# schematic.net
KiCad netlist of a schematic drawn in EasyEDA
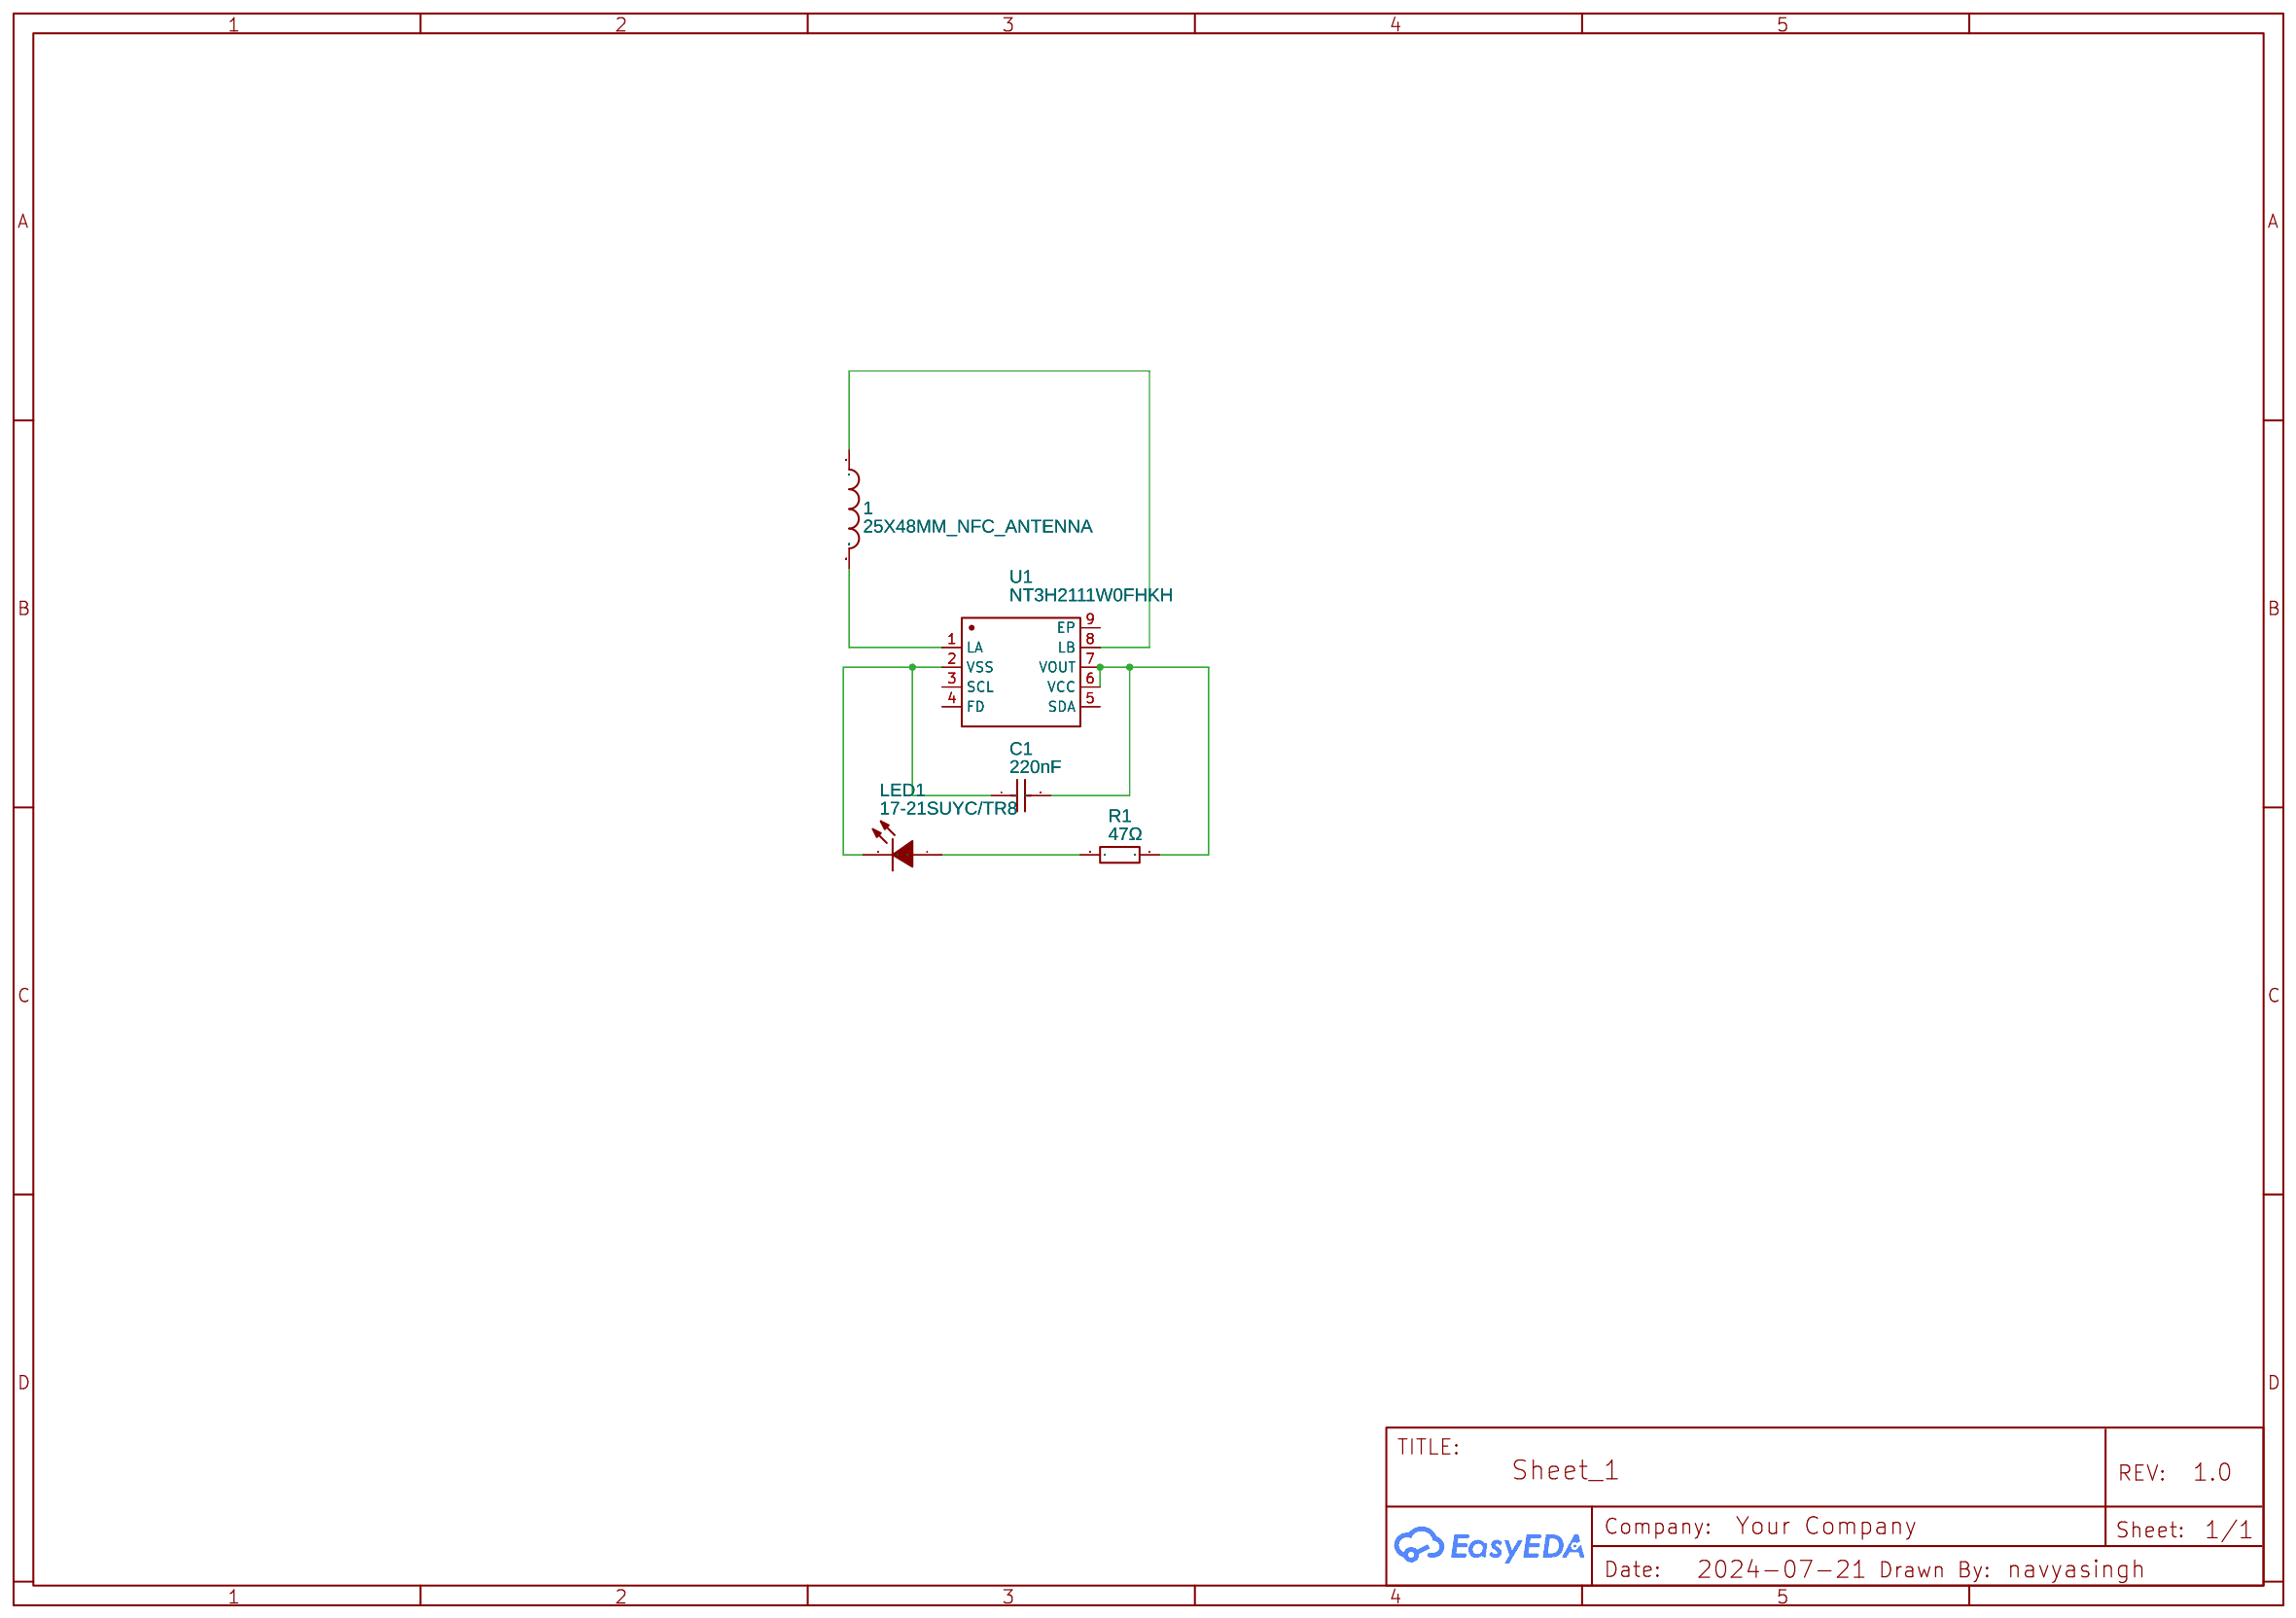
[diagram p0: schematic sheet]

(export (version "E")
  (design (tool "Eeschema 10.0.6"))
  (components
    (comp (ref "1") (value "25X48MM_NFC_ANTENNA") (libsource (lib "") (part "25X48MM_NFC_ANTENNA")))
    (comp (ref "C1")
      (value "220nF")
      (fields
        (field (name "Manufacturer Part") "CL10B224KA8NNNC")
        (field (name "Manufacturer") "SAMSUNG(三星)")
      )
      (libsource (lib "") (part "CL10B224KA8NNNC"))
    )
    (comp (ref "LED1")
      (value "17-21SUYC/TR8")
      (fields (field (name "Manufacturer Part") "KT-0805黄灯") (field (name "Manufacturer") "KENTO"))
      (libsource (lib "") (part "17-21SUYC/TR8"))
    )
    (comp (ref "R1")
      (value "47Ω")
      (fields
        (field (name "Manufacturer Part") "0603WAF470JT5E")
        (field (name "Manufacturer") "UNI-ROYAL(厚声)")
      )
      (libsource (lib "") (part "0603WAF470JT5E"))
    )
    (comp (ref "U1")
      (value "NT3H2111W0FHKH")
      (fields (field (name "Manufacturer") "NXP(恩智浦)"))
      (libsource (lib "") (part "NT3H2111W0FHKH"))
    )
  )
  (nets
    (net (code "1") (name "Net-(LED1-+)") (class "Default")
      (node (ref "LED1") (pin "1") (pinfunction "+_1") (pintype "unspecified"))
      (node (ref "R1") (pin "1") (pinfunction "1_1") (pintype "input"))
    )
    (net (code "2") (name "Net-(LED1--)") (class "Default")
      (node (ref "C1") (pin "1") (pinfunction "1_1") (pintype "input"))
      (node (ref "LED1") (pin "2") (pinfunction "-_2") (pintype "unspecified"))
      (node (ref "U1") (pin "2") (pinfunction "VSS_2") (pintype "unspecified"))
    )
    (net (code "3") (name "Net-(U1-LA)") (class "Default")
      (node (ref "1") (pin "P$2") (pinfunction "P$2_P$2") (pintype "bidirectional"))
      (node (ref "U1") (pin "1") (pinfunction "LA_1") (pintype "unspecified"))
    )
    (net (code "4") (name "Net-(U1-LB)") (class "Default")
      (node (ref "1") (pin "P$1") (pinfunction "P$1_P$1") (pintype "bidirectional"))
      (node (ref "U1") (pin "8") (pinfunction "LB_8") (pintype "unspecified"))
    )
    (net (code "5") (name "Net-(U1-VCC)") (class "Default")
      (node (ref "C1") (pin "2") (pinfunction "2_2") (pintype "input"))
      (node (ref "R1") (pin "2") (pinfunction "2_2") (pintype "input"))
      (node (ref "U1") (pin "6") (pinfunction "VCC_6") (pintype "unspecified"))
      (node (ref "U1") (pin "7") (pinfunction "VOUT_7") (pintype "unspecified"))
    )
    (net (code "6") (name "unconnected-(U1-EP-Pad9)") (class "Default")
      (node (ref "U1") (pin "9") (pinfunction "EP_9") (pintype "unspecified"))
    )
    (net (code "7") (name "unconnected-(U1-FD-Pad4)") (class "Default")
      (node (ref "U1") (pin "4") (pinfunction "FD_4") (pintype "unspecified"))
    )
    (net (code "8") (name "unconnected-(U1-SCL-Pad3)") (class "Default")
      (node (ref "U1") (pin "3") (pinfunction "SCL_3") (pintype "unspecified"))
    )
    (net (code "9") (name "unconnected-(U1-SDA-Pad5)") (class "Default")
      (node (ref "U1") (pin "5") (pinfunction "SDA_5") (pintype "unspecified"))
    )
  )
)
